# esquematico.net
KiCad netlist of a schematic drawn in EAGLE
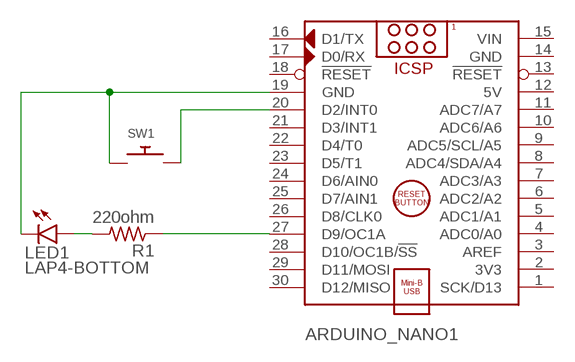
[diagram p0: schematic, sheet 1]

(export (version "E")
  (design (tool "Eeschema 10.0.6"))
  (components
    (comp (ref "ARDUINO_NANO1")
      (value "ARDUINO_NANO")
      (footprint "eagle-import:ARDUINO_NANO")
      (libsource (lib "eagle-import") (part "ARDUINO_NANO"))
    )
    (comp (ref "LED1")
      (value "LAP4-BOTTOM")
      (footprint "eagle-import:P47F-BOTTOM")
      (libsource (lib "eagle-import") (part "P4-BOTTOMLA"))
    )
    (comp (ref "R1")
      (value "220ohm")
      (footprint "eagle-import:0414_15")
      (libsource (lib "eagle-import") (part "R-US_0414/15"))
    )
    (comp (ref "SW1")
      (value "SWITCH_PUSHBUTTONEVQ-PE")
      (footprint "eagle-import:TACT_PANA-EVQ")
      (libsource (lib "eagle-import") (part "SWITCH_PUSHBUTTONEVQ-PE"))
    )
  )
  (nets
    (net (code "1") (name "/5V") (class "Default")
      (node (ref "ARDUINO_NANO1") (pin "12") (pinfunction "5V_12") (pintype "power_in"))
    )
    (net (code "2") (name "/GND") (class "Default")
      (node (ref "ARDUINO_NANO1") (pin "14") (pinfunction "GND_14") (pintype "power_in"))
    )
    (net (code "3") (name "/VIN") (class "Default")
      (node (ref "ARDUINO_NANO1") (pin "15") (pinfunction "VIN_15") (pintype "power_in"))
    )
    (net (code "4") (name "Net-(ARDUINO_NANO1-D2{slash}INT0)") (class "Default")
      (node (ref "ARDUINO_NANO1") (pin "20") (pinfunction "D2/INT0_20") (pintype "bidirectional"))
      (node (ref "SW1") (pin "P$2") (pinfunction "P$2_P$2") (pintype "passive"))
    )
    (net (code "5") (name "Net-(ARDUINO_NANO1-D9{slash}OC1A)") (class "Default")
      (node (ref "ARDUINO_NANO1") (pin "27") (pinfunction "D9/OC1A_27") (pintype "bidirectional"))
      (node (ref "R1") (pin "1") (pinfunction "1_1") (pintype "passive"))
    )
    (net (code "6") (name "Net-(ARDUINO_NANO1-GND-Pad19)") (class "Default")
      (node (ref "ARDUINO_NANO1") (pin "19") (pinfunction "GND_19") (pintype "power_in"))
      (node (ref "LED1") (pin "C") (pinfunction "C_C") (pintype "passive"))
      (node (ref "SW1") (pin "P$1") (pinfunction "P$1_P$1") (pintype "passive"))
    )
    (net (code "7") (name "Net-(LED1-PadA)") (class "Default")
      (node (ref "LED1") (pin "A") (pinfunction "A_A") (pintype "passive"))
      (node (ref "R1") (pin "2") (pinfunction "2_2") (pintype "passive"))
    )
    (net (code "8") (name "unconnected-(ARDUINO_NANO1-3V3-Pad2)") (class "Default")
      (node (ref "ARDUINO_NANO1") (pin "2") (pinfunction "3V3_2") (pintype "output"))
    )
    (net (code "9") (name "unconnected-(ARDUINO_NANO1-ADC0{slash}A0-Pad4)") (class "Default")
      (node (ref "ARDUINO_NANO1") (pin "4") (pinfunction "ADC0/A0_4") (pintype "bidirectional"))
    )
    (net (code "10") (name "unconnected-(ARDUINO_NANO1-ADC1{slash}A1-Pad5)") (class "Default")
      (node (ref "ARDUINO_NANO1") (pin "5") (pinfunction "ADC1/A1_5") (pintype "bidirectional"))
    )
    (net (code "11") (name "unconnected-(ARDUINO_NANO1-ADC2{slash}A2-Pad6)") (class "Default")
      (node (ref "ARDUINO_NANO1") (pin "6") (pinfunction "ADC2/A2_6") (pintype "bidirectional"))
    )
    (net (code "12") (name "unconnected-(ARDUINO_NANO1-ADC3{slash}A3-Pad7)") (class "Default")
      (node (ref "ARDUINO_NANO1") (pin "7") (pinfunction "ADC3/A3_7") (pintype "bidirectional"))
    )
    (net (code "13") (name "unconnected-(ARDUINO_NANO1-ADC4{slash}SDA{slash}A4-Pad8)") (class "Default")
      (node (ref "ARDUINO_NANO1") (pin "8") (pinfunction "ADC4/SDA/A4_8") (pintype "bidirectional"))
    )
    (net (code "14") (name "unconnected-(ARDUINO_NANO1-ADC5{slash}SCL{slash}A5-Pad9)") (class "Default")
      (node (ref "ARDUINO_NANO1") (pin "9") (pinfunction "ADC5/SCL/A5_9") (pintype "bidirectional"))
    )
    (net (code "15") (name "unconnected-(ARDUINO_NANO1-ADC6{slash}A6-Pad10)") (class "Default")
      (node (ref "ARDUINO_NANO1") (pin "10") (pinfunction "ADC6/A6_10") (pintype "bidirectional"))
    )
    (net (code "16") (name "unconnected-(ARDUINO_NANO1-ADC7{slash}A7-Pad11)") (class "Default")
      (node (ref "ARDUINO_NANO1") (pin "11") (pinfunction "ADC7/A7_11") (pintype "bidirectional"))
    )
    (net (code "17") (name "unconnected-(ARDUINO_NANO1-AREF-Pad3)") (class "Default")
      (node (ref "ARDUINO_NANO1") (pin "3") (pinfunction "AREF_3") (pintype "input"))
    )
    (net (code "18") (name "unconnected-(ARDUINO_NANO1-D0{slash}RX-Pad17)") (class "Default")
      (node (ref "ARDUINO_NANO1") (pin "17") (pinfunction "D0/RX_17") (pintype "bidirectional"))
    )
    (net (code "19") (name "unconnected-(ARDUINO_NANO1-D1{slash}TX-Pad16)") (class "Default")
      (node (ref "ARDUINO_NANO1") (pin "16") (pinfunction "D1/TX_16") (pintype "bidirectional"))
    )
    (net (code "20") (name "unconnected-(ARDUINO_NANO1-D3{slash}INT1-Pad21)") (class "Default")
      (node (ref "ARDUINO_NANO1") (pin "21") (pinfunction "D3/INT1_21") (pintype "bidirectional"))
    )
    (net (code "21") (name "unconnected-(ARDUINO_NANO1-D4{slash}T0-Pad22)") (class "Default")
      (node (ref "ARDUINO_NANO1") (pin "22") (pinfunction "D4/T0_22") (pintype "bidirectional"))
    )
    (net (code "22") (name "unconnected-(ARDUINO_NANO1-D5{slash}T1-Pad23)") (class "Default")
      (node (ref "ARDUINO_NANO1") (pin "23") (pinfunction "D5/T1_23") (pintype "bidirectional"))
    )
    (net (code "23") (name "unconnected-(ARDUINO_NANO1-D6{slash}AIN0-Pad24)") (class "Default")
      (node (ref "ARDUINO_NANO1") (pin "24") (pinfunction "D6/AIN0_24") (pintype "bidirectional"))
    )
    (net (code "24") (name "unconnected-(ARDUINO_NANO1-D7{slash}AIN1-Pad25)") (class "Default")
      (node (ref "ARDUINO_NANO1") (pin "25") (pinfunction "D7/AIN1_25") (pintype "bidirectional"))
    )
    (net (code "25") (name "unconnected-(ARDUINO_NANO1-D8{slash}CLK0-Pad26)") (class "Default")
      (node (ref "ARDUINO_NANO1") (pin "26") (pinfunction "D8/CLK0_26") (pintype "bidirectional"))
    )
    (net (code "26") (name "unconnected-(ARDUINO_NANO1-D10{slash}OC1B{slash}~{SS}-Pad28)") (class "Default")
      (node (ref "ARDUINO_NANO1") (pin "28") (pinfunction "D10/OC1B/~{SS}_28") (pintype "bidirectional"))
    )
    (net (code "27") (name "unconnected-(ARDUINO_NANO1-D11{slash}MOSI-Pad29)") (class "Default")
      (node (ref "ARDUINO_NANO1") (pin "29") (pinfunction "D11/MOSI_29") (pintype "bidirectional"))
    )
    (net (code "28") (name "unconnected-(ARDUINO_NANO1-D12{slash}MISO-Pad30)") (class "Default")
      (node (ref "ARDUINO_NANO1") (pin "30") (pinfunction "D12/MISO_30") (pintype "bidirectional"))
    )
    (net (code "29") (name "unconnected-(ARDUINO_NANO1-SCK{slash}D13-Pad1)") (class "Default")
      (node (ref "ARDUINO_NANO1") (pin "1") (pinfunction "SCK/D13_1") (pintype "bidirectional"))
    )
    (net (code "30") (name "unconnected-(ARDUINO_NANO1-~{RESET}-Pad13)") (class "Default")
      (node (ref "ARDUINO_NANO1") (pin "13") (pinfunction "~{RESET}_13") (pintype "input"))
    )
    (net (code "31") (name "unconnected-(ARDUINO_NANO1-~{RESET}-Pad18)") (class "Default")
      (node (ref "ARDUINO_NANO1") (pin "18") (pinfunction "~{RESET}_18") (pintype "input"))
    )
  )
)
